# Steering_board.net
KiCad netlist of a schematic drawn in EAGLE
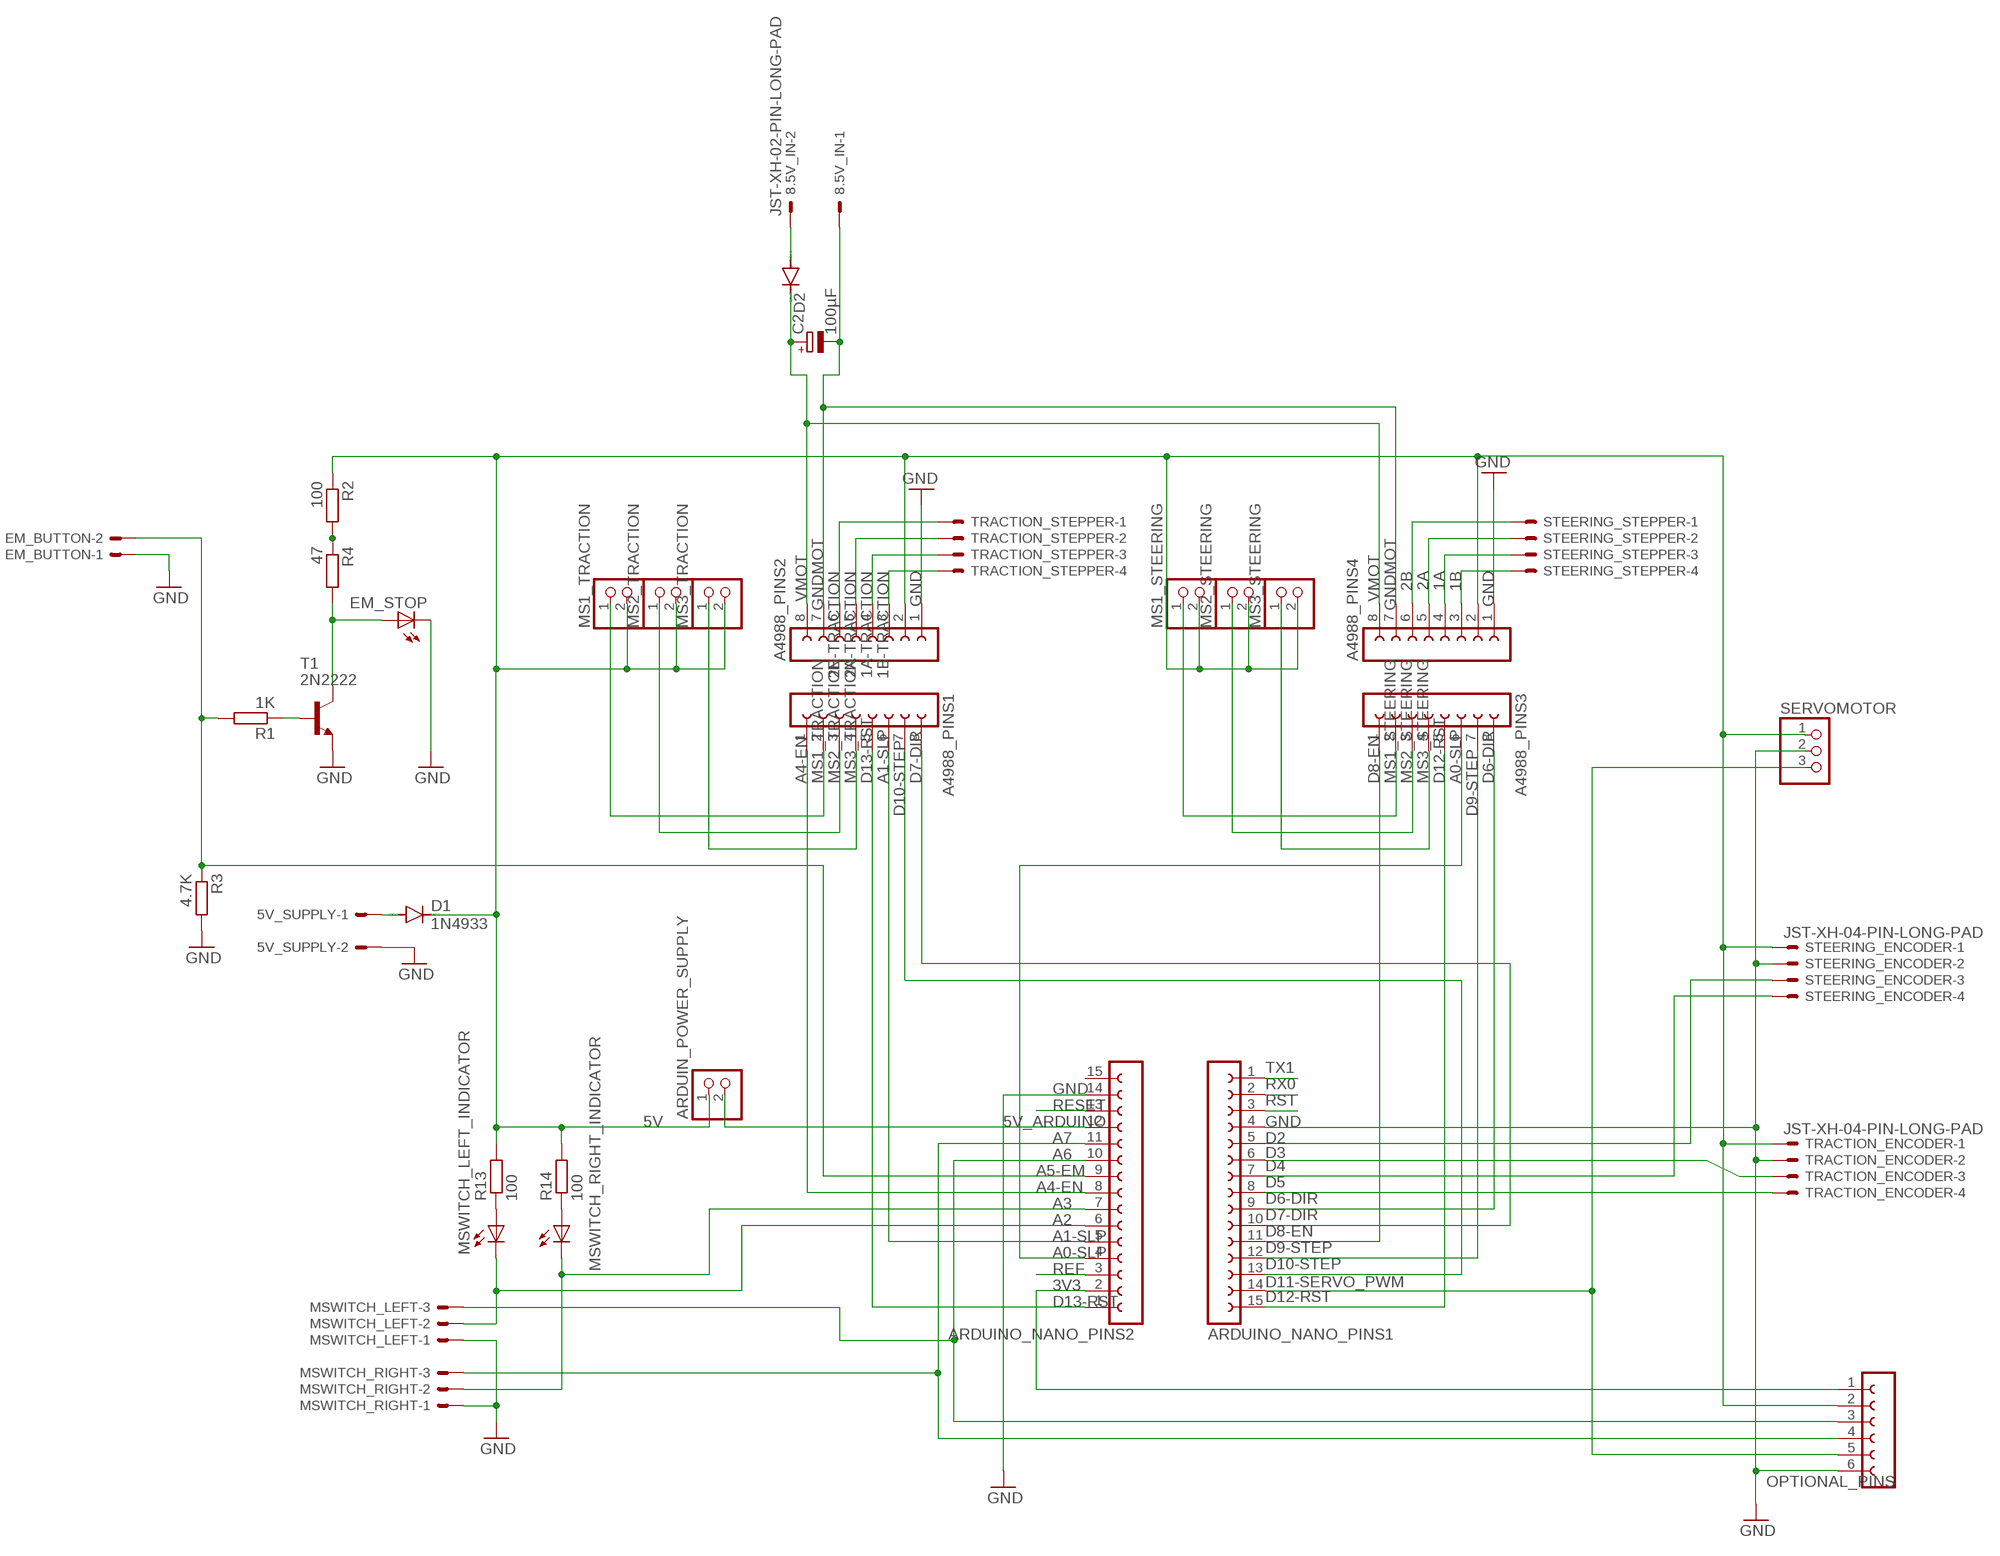
[diagram p0: schematic, sheet 1]

(export (version "E")
  (design (tool "Eeschema 10.0.6"))
  (components
    (comp (ref "5V_SUPPLY")
      (value "JST-XH-02-PIN-LONG-PAD")
      (footprint "eagle-import:JST-XH-02-PACKAGE-LONG-PAD")
      (libsource (lib "eagle-import") (part "JST-XH-02-PIN-LONG-PAD"))
    )
    (comp (ref "8.5V_IN")
      (value "JST-XH-02-PIN-LONG-PAD")
      (footprint "eagle-import:JST-XH-02-PACKAGE-LONG-PAD")
      (libsource (lib "eagle-import") (part "JST-XH-02-PIN-LONG-PAD"))
    )
    (comp (ref "A4988_PINS1")
      (value "FE08-1")
      (footprint "eagle-import:FE08")
      (libsource (lib "eagle-import") (part "FE08-1"))
    )
    (comp (ref "A4988_PINS2")
      (value "FE08-1")
      (footprint "eagle-import:FE08")
      (libsource (lib "eagle-import") (part "FE08-1"))
    )
    (comp (ref "A4988_PINS3")
      (value "FE08-1")
      (footprint "eagle-import:FE08")
      (libsource (lib "eagle-import") (part "FE08-1"))
    )
    (comp (ref "A4988_PINS4")
      (value "FE08-1")
      (footprint "eagle-import:FE08")
      (libsource (lib "eagle-import") (part "FE08-1"))
    )
    (comp (ref "ARDUINO_NANO_PINS1")
      (value "FE15-1")
      (footprint "eagle-import:FE15")
      (libsource (lib "eagle-import") (part "FE15-1"))
    )
    (comp (ref "ARDUINO_NANO_PINS2")
      (value "FE15-1")
      (footprint "eagle-import:FE15")
      (libsource (lib "eagle-import") (part "FE15-1"))
    )
    (comp (ref "ARDUIN_POWER_SUPPLY")
      (value "PINHD-1X2")
      (footprint "eagle-import:1X02")
      (libsource (lib "eagle-import") (part "PINHD-1X2"))
    )
    (comp (ref "C2")
      (value "100µF")
      (footprint "eagle-import:SANYO-OSCON_E")
      (libsource (lib "eagle-import") (part "CPOL-EUSANYO_E"))
    )
    (comp (ref "D1")
      (value "1N4933")
      (footprint "eagle-import:DO41-10")
      (libsource (lib "eagle-import") (part "1N4933"))
    )
    (comp (ref "D2")
      (value "DIODE-DO15-12")
      (footprint "eagle-import:DO15-12")
      (libsource (lib "eagle-import") (part "DIODE-DO15-12"))
    )
    (comp (ref "EM_BUTTON")
      (value "JST-XH-02-PIN-LONG-PAD")
      (footprint "eagle-import:JST-XH-02-PACKAGE-LONG-PAD")
      (libsource (lib "eagle-import") (part "JST-XH-02-PIN-LONG-PAD"))
    )
    (comp (ref "EM_STOP")
      (value "LED5MM")
      (footprint "eagle-import:LED5MM")
      (libsource (lib "eagle-import") (part "LED5MM"))
    )
    (comp (ref "MS1_STEERING")
      (value "PINHD-1X2")
      (footprint "eagle-import:1X02")
      (libsource (lib "eagle-import") (part "PINHD-1X2"))
    )
    (comp (ref "MS1_TRACTION")
      (value "PINHD-1X2")
      (footprint "eagle-import:1X02")
      (libsource (lib "eagle-import") (part "PINHD-1X2"))
    )
    (comp (ref "MS2_STEERING")
      (value "PINHD-1X2")
      (footprint "eagle-import:1X02")
      (libsource (lib "eagle-import") (part "PINHD-1X2"))
    )
    (comp (ref "MS2_TRACTION")
      (value "PINHD-1X2")
      (footprint "eagle-import:1X02")
      (libsource (lib "eagle-import") (part "PINHD-1X2"))
    )
    (comp (ref "MS3_STEERING")
      (value "PINHD-1X2")
      (footprint "eagle-import:1X02")
      (libsource (lib "eagle-import") (part "PINHD-1X2"))
    )
    (comp (ref "MS3_TRACTION")
      (value "PINHD-1X2")
      (footprint "eagle-import:1X02")
      (libsource (lib "eagle-import") (part "PINHD-1X2"))
    )
    (comp (ref "MSWITCH_LEFT")
      (value "JST-XH-03-PIN-LONG-PAD")
      (footprint "eagle-import:JST-XH-03-PACKAGE-LONG-PAD")
      (libsource (lib "eagle-import") (part "JST-XH-03-PIN-LONG-PAD"))
    )
    (comp (ref "MSWITCH_LEFT_INDICATOR")
      (value "LED5MM")
      (footprint "eagle-import:LED5MM")
      (libsource (lib "eagle-import") (part "LED5MM"))
    )
    (comp (ref "MSWITCH_RIGHT")
      (value "JST-XH-03-PIN-LONG-PAD")
      (footprint "eagle-import:JST-XH-03-PACKAGE-LONG-PAD")
      (libsource (lib "eagle-import") (part "JST-XH-03-PIN-LONG-PAD"))
    )
    (comp (ref "MSWITCH_RIGHT_INDICATOR")
      (value "LED5MM")
      (footprint "eagle-import:LED5MM")
      (libsource (lib "eagle-import") (part "LED5MM"))
    )
    (comp (ref "OPTIONAL_PINS")
      (value "FE06-1")
      (footprint "eagle-import:FE06")
      (libsource (lib "eagle-import") (part "FE06-1"))
    )
    (comp (ref "R1")
      (value "1K")
      (footprint "eagle-import:0207_7")
      (libsource (lib "eagle-import") (part "R-EU_0207/7"))
    )
    (comp (ref "R2")
      (value "100")
      (footprint "eagle-import:0207_7")
      (libsource (lib "eagle-import") (part "R-EU_0207/7"))
    )
    (comp (ref "R3")
      (value "4.7K")
      (footprint "eagle-import:0207_7")
      (libsource (lib "eagle-import") (part "R-EU_0207/7"))
    )
    (comp (ref "R4")
      (value "47")
      (footprint "eagle-import:0207_7")
      (libsource (lib "eagle-import") (part "R-EU_0207/7"))
    )
    (comp (ref "R13")
      (value "100")
      (footprint "eagle-import:0207_7")
      (libsource (lib "eagle-import") (part "R-EU_0207/7"))
    )
    (comp (ref "R14")
      (value "100")
      (footprint "eagle-import:0207_7")
      (libsource (lib "eagle-import") (part "R-EU_0207/7"))
    )
    (comp (ref "SERVOMOTOR")
      (value "PINHD-1X3")
      (footprint "eagle-import:1X03")
      (libsource (lib "eagle-import") (part "PINHD-1X3"))
    )
    (comp (ref "STEERING_ENCODER")
      (value "JST-XH-04-PIN-LONG-PAD")
      (footprint "eagle-import:JST-XH-04-PACKAGE-LONG-PAD")
      (libsource (lib "eagle-import") (part "JST-XH-04-PIN-LONG-PAD"))
    )
    (comp (ref "STEERING_STEPPER")
      (value "JST-XH-04-PIN-LONG-PAD")
      (footprint "eagle-import:JST-XH-04-PACKAGE-LONG-PAD")
      (libsource (lib "eagle-import") (part "JST-XH-04-PIN-LONG-PAD"))
    )
    (comp (ref "T1")
      (value "2N2222")
      (footprint "eagle-import:TO92-EBC-OVAL")
      (libsource (lib "eagle-import") (part "2N2222"))
    )
    (comp (ref "TRACTION_ENCODER")
      (value "JST-XH-04-PIN-LONG-PAD")
      (footprint "eagle-import:JST-XH-04-PACKAGE-LONG-PAD")
      (libsource (lib "eagle-import") (part "JST-XH-04-PIN-LONG-PAD"))
    )
    (comp (ref "TRACTION_STEPPER")
      (value "JST-XH-04-PIN-LONG-PAD")
      (footprint "eagle-import:JST-XH-04-PACKAGE-LONG-PAD")
      (libsource (lib "eagle-import") (part "JST-XH-04-PIN-LONG-PAD"))
    )
  )
  (nets
    (net (code "1") (name "/1A") (class "Default")
      (node (ref "A4988_PINS4") (pin "4") (pinfunction "4_4") (pintype "passive"))
      (node (ref "STEERING_STEPPER") (pin "3") (pinfunction "S_3") (pintype "passive"))
    )
    (net (code "2") (name "/1A-TRACTION") (class "Default")
      (node (ref "A4988_PINS2") (pin "4") (pinfunction "4_4") (pintype "passive"))
      (node (ref "TRACTION_STEPPER") (pin "3") (pinfunction "S_3") (pintype "passive"))
    )
    (net (code "3") (name "/1B") (class "Default")
      (node (ref "A4988_PINS4") (pin "3") (pinfunction "3_3") (pintype "passive"))
      (node (ref "STEERING_STEPPER") (pin "4") (pinfunction "S_4") (pintype "passive"))
    )
    (net (code "4") (name "/1B-TRACTION") (class "Default")
      (node (ref "A4988_PINS2") (pin "3") (pinfunction "3_3") (pintype "passive"))
      (node (ref "TRACTION_STEPPER") (pin "4") (pinfunction "S_4") (pintype "passive"))
    )
    (net (code "5") (name "/2A") (class "Default")
      (node (ref "A4988_PINS4") (pin "5") (pinfunction "5_5") (pintype "passive"))
      (node (ref "STEERING_STEPPER") (pin "2") (pinfunction "S_2") (pintype "passive"))
    )
    (net (code "6") (name "/2A-TRACTION") (class "Default")
      (node (ref "A4988_PINS2") (pin "5") (pinfunction "5_5") (pintype "passive"))
      (node (ref "TRACTION_STEPPER") (pin "2") (pinfunction "S_2") (pintype "passive"))
    )
    (net (code "7") (name "/2B") (class "Default")
      (node (ref "A4988_PINS4") (pin "6") (pinfunction "6_6") (pintype "passive"))
      (node (ref "STEERING_STEPPER") (pin "1") (pinfunction "S_1") (pintype "passive"))
    )
    (net (code "8") (name "/2B-TRACTION") (class "Default")
      (node (ref "A4988_PINS2") (pin "6") (pinfunction "6_6") (pintype "passive"))
      (node (ref "TRACTION_STEPPER") (pin "1") (pinfunction "S_1") (pintype "passive"))
    )
    (net (code "9") (name "/3V3") (class "Default")
      (node (ref "ARDUINO_NANO_PINS2") (pin "2") (pinfunction "2_2") (pintype "passive"))
      (node (ref "OPTIONAL_PINS") (pin "1") (pinfunction "1_1") (pintype "passive"))
    )
    (net (code "10") (name "/5V") (class "Default")
      (node (ref "A4988_PINS2") (pin "2") (pinfunction "2_2") (pintype "passive"))
      (node (ref "A4988_PINS4") (pin "2") (pinfunction "2_2") (pintype "passive"))
      (node (ref "ARDUIN_POWER_SUPPLY") (pin "1") (pinfunction "1_1") (pintype "passive"))
      (node (ref "D1") (pin "C") (pinfunction "C_C") (pintype "passive"))
      (node (ref "MS1_STEERING") (pin "2") (pinfunction "2_2") (pintype "passive"))
      (node (ref "MS1_TRACTION") (pin "2") (pinfunction "2_2") (pintype "passive"))
      (node (ref "MS2_STEERING") (pin "2") (pinfunction "2_2") (pintype "passive"))
      (node (ref "MS2_TRACTION") (pin "2") (pinfunction "2_2") (pintype "passive"))
      (node (ref "MS3_STEERING") (pin "2") (pinfunction "2_2") (pintype "passive"))
      (node (ref "MS3_TRACTION") (pin "2") (pinfunction "2_2") (pintype "passive"))
      (node (ref "OPTIONAL_PINS") (pin "2") (pinfunction "2_2") (pintype "passive"))
      (node (ref "R13") (pin "2") (pinfunction "2_2") (pintype "passive"))
      (node (ref "R14") (pin "2") (pinfunction "2_2") (pintype "passive"))
      (node (ref "R2") (pin "1") (pinfunction "1_1") (pintype "passive"))
      (node (ref "SERVOMOTOR") (pin "1") (pinfunction "1_1") (pintype "passive"))
      (node (ref "STEERING_ENCODER") (pin "1") (pinfunction "S_1") (pintype "passive"))
      (node (ref "TRACTION_ENCODER") (pin "1") (pinfunction "S_1") (pintype "passive"))
    )
    (net (code "11") (name "/5V_ARDUINO") (class "Default")
      (node (ref "ARDUINO_NANO_PINS2") (pin "12") (pinfunction "12_12") (pintype "passive"))
      (node (ref "ARDUIN_POWER_SUPPLY") (pin "2") (pinfunction "2_2") (pintype "passive"))
    )
    (net (code "12") (name "/A0-SLP") (class "Default")
      (node (ref "A4988_PINS3") (pin "6") (pinfunction "6_6") (pintype "passive"))
      (node (ref "ARDUINO_NANO_PINS2") (pin "4") (pinfunction "4_4") (pintype "passive"))
    )
    (net (code "13") (name "/A1-SLP") (class "Default")
      (node (ref "A4988_PINS1") (pin "6") (pinfunction "6_6") (pintype "passive"))
      (node (ref "ARDUINO_NANO_PINS2") (pin "5") (pinfunction "5_5") (pintype "passive"))
    )
    (net (code "14") (name "/A2") (class "Default")
      (node (ref "ARDUINO_NANO_PINS2") (pin "6") (pinfunction "6_6") (pintype "passive"))
      (node (ref "MSWITCH_LEFT") (pin "2") (pinfunction "S_2") (pintype "passive"))
      (node (ref "MSWITCH_LEFT_INDICATOR") (pin "K") (pinfunction "C_K") (pintype "passive"))
    )
    (net (code "15") (name "/A3") (class "Default")
      (node (ref "ARDUINO_NANO_PINS2") (pin "7") (pinfunction "7_7") (pintype "passive"))
      (node (ref "MSWITCH_RIGHT") (pin "2") (pinfunction "S_2") (pintype "passive"))
      (node (ref "MSWITCH_RIGHT_INDICATOR") (pin "K") (pinfunction "C_K") (pintype "passive"))
    )
    (net (code "16") (name "/A4-EN") (class "Default")
      (node (ref "A4988_PINS1") (pin "1") (pinfunction "1_1") (pintype "passive"))
      (node (ref "ARDUINO_NANO_PINS2") (pin "8") (pinfunction "8_8") (pintype "passive"))
    )
    (net (code "17") (name "/A5-EM") (class "Default")
      (node (ref "ARDUINO_NANO_PINS2") (pin "9") (pinfunction "9_9") (pintype "passive"))
      (node (ref "EM_BUTTON") (pin "2") (pinfunction "S_2") (pintype "passive"))
      (node (ref "R1") (pin "2") (pinfunction "2_2") (pintype "passive"))
      (node (ref "R3") (pin "1") (pinfunction "1_1") (pintype "passive"))
    )
    (net (code "18") (name "/A6") (class "Default")
      (node (ref "ARDUINO_NANO_PINS2") (pin "10") (pinfunction "10_10") (pintype "passive"))
      (node (ref "MSWITCH_LEFT") (pin "3") (pinfunction "S_3") (pintype "passive"))
      (node (ref "OPTIONAL_PINS") (pin "3") (pinfunction "3_3") (pintype "passive"))
    )
    (net (code "19") (name "/A7") (class "Default")
      (node (ref "ARDUINO_NANO_PINS2") (pin "11") (pinfunction "11_11") (pintype "passive"))
      (node (ref "MSWITCH_RIGHT") (pin "3") (pinfunction "S_3") (pintype "passive"))
      (node (ref "OPTIONAL_PINS") (pin "4") (pinfunction "4_4") (pintype "passive"))
    )
    (net (code "20") (name "/D2") (class "Default")
      (node (ref "ARDUINO_NANO_PINS1") (pin "5") (pinfunction "5_5") (pintype "passive"))
      (node (ref "STEERING_ENCODER") (pin "3") (pinfunction "S_3") (pintype "passive"))
    )
    (net (code "21") (name "/D3") (class "Default")
      (node (ref "ARDUINO_NANO_PINS1") (pin "6") (pinfunction "6_6") (pintype "passive"))
      (node (ref "TRACTION_ENCODER") (pin "3") (pinfunction "S_3") (pintype "passive"))
    )
    (net (code "22") (name "/D4") (class "Default")
      (node (ref "ARDUINO_NANO_PINS1") (pin "7") (pinfunction "7_7") (pintype "passive"))
      (node (ref "STEERING_ENCODER") (pin "4") (pinfunction "S_4") (pintype "passive"))
    )
    (net (code "23") (name "/D5") (class "Default")
      (node (ref "ARDUINO_NANO_PINS1") (pin "8") (pinfunction "8_8") (pintype "passive"))
      (node (ref "TRACTION_ENCODER") (pin "4") (pinfunction "S_4") (pintype "passive"))
    )
    (net (code "24") (name "/D6-DIR") (class "Default")
      (node (ref "A4988_PINS3") (pin "8") (pinfunction "8_8") (pintype "passive"))
      (node (ref "ARDUINO_NANO_PINS1") (pin "9") (pinfunction "9_9") (pintype "passive"))
    )
    (net (code "25") (name "/D7-DIR") (class "Default")
      (node (ref "A4988_PINS1") (pin "8") (pinfunction "8_8") (pintype "passive"))
      (node (ref "ARDUINO_NANO_PINS1") (pin "10") (pinfunction "10_10") (pintype "passive"))
    )
    (net (code "26") (name "/D8-EN") (class "Default")
      (node (ref "A4988_PINS3") (pin "1") (pinfunction "1_1") (pintype "passive"))
      (node (ref "ARDUINO_NANO_PINS1") (pin "11") (pinfunction "11_11") (pintype "passive"))
    )
    (net (code "27") (name "/D9-STEP") (class "Default")
      (node (ref "A4988_PINS3") (pin "7") (pinfunction "7_7") (pintype "passive"))
      (node (ref "ARDUINO_NANO_PINS1") (pin "12") (pinfunction "12_12") (pintype "passive"))
    )
    (net (code "28") (name "/D10-STEP") (class "Default")
      (node (ref "A4988_PINS1") (pin "7") (pinfunction "7_7") (pintype "passive"))
      (node (ref "ARDUINO_NANO_PINS1") (pin "13") (pinfunction "13_13") (pintype "passive"))
    )
    (net (code "29") (name "/D11-SERVO_PWM") (class "Default")
      (node (ref "ARDUINO_NANO_PINS1") (pin "14") (pinfunction "14_14") (pintype "passive"))
      (node (ref "OPTIONAL_PINS") (pin "5") (pinfunction "5_5") (pintype "passive"))
      (node (ref "SERVOMOTOR") (pin "3") (pinfunction "3_3") (pintype "passive"))
    )
    (net (code "30") (name "/D12-RST") (class "Default")
      (node (ref "A4988_PINS3") (pin "5") (pinfunction "5_5") (pintype "passive"))
      (node (ref "ARDUINO_NANO_PINS1") (pin "15") (pinfunction "15_15") (pintype "passive"))
    )
    (net (code "31") (name "/D13-RST") (class "Default")
      (node (ref "A4988_PINS1") (pin "5") (pinfunction "5_5") (pintype "passive"))
      (node (ref "ARDUINO_NANO_PINS2") (pin "1") (pinfunction "1_1") (pintype "passive"))
    )
    (net (code "32") (name "/GNDMOT") (class "Default")
      (node (ref "8.5V_IN") (pin "1") (pinfunction "S_1") (pintype "passive"))
      (node (ref "A4988_PINS2") (pin "7") (pinfunction "7_7") (pintype "passive"))
      (node (ref "A4988_PINS4") (pin "7") (pinfunction "7_7") (pintype "passive"))
      (node (ref "C2") (pin "-") (pinfunction "-_-") (pintype "passive"))
    )
    (net (code "33") (name "/MS1_STEERING") (class "Default")
      (node (ref "A4988_PINS3") (pin "2") (pinfunction "2_2") (pintype "passive"))
      (node (ref "MS1_STEERING") (pin "1") (pinfunction "1_1") (pintype "passive"))
    )
    (net (code "34") (name "/MS1_TRACTION") (class "Default")
      (node (ref "A4988_PINS1") (pin "2") (pinfunction "2_2") (pintype "passive"))
      (node (ref "MS1_TRACTION") (pin "1") (pinfunction "1_1") (pintype "passive"))
    )
    (net (code "35") (name "/MS2_STEERING") (class "Default")
      (node (ref "A4988_PINS3") (pin "3") (pinfunction "3_3") (pintype "passive"))
      (node (ref "MS2_STEERING") (pin "1") (pinfunction "1_1") (pintype "passive"))
    )
    (net (code "36") (name "/MS2_TRACTION") (class "Default")
      (node (ref "A4988_PINS1") (pin "3") (pinfunction "3_3") (pintype "passive"))
      (node (ref "MS2_TRACTION") (pin "1") (pinfunction "1_1") (pintype "passive"))
    )
    (net (code "37") (name "/MS3_STEERING") (class "Default")
      (node (ref "A4988_PINS3") (pin "4") (pinfunction "4_4") (pintype "passive"))
      (node (ref "MS3_STEERING") (pin "1") (pinfunction "1_1") (pintype "passive"))
    )
    (net (code "38") (name "/MS3_TRACTION") (class "Default")
      (node (ref "A4988_PINS1") (pin "4") (pinfunction "4_4") (pintype "passive"))
      (node (ref "MS3_TRACTION") (pin "1") (pinfunction "1_1") (pintype "passive"))
    )
    (net (code "39") (name "/REF") (class "Default")
      (node (ref "ARDUINO_NANO_PINS2") (pin "3") (pinfunction "3_3") (pintype "passive"))
    )
    (net (code "40") (name "/RESET") (class "Default")
      (node (ref "ARDUINO_NANO_PINS2") (pin "13") (pinfunction "13_13") (pintype "passive"))
    )
    (net (code "41") (name "/RST") (class "Default")
      (node (ref "ARDUINO_NANO_PINS1") (pin "3") (pinfunction "3_3") (pintype "passive"))
    )
    (net (code "42") (name "/RX0") (class "Default")
      (node (ref "ARDUINO_NANO_PINS1") (pin "2") (pinfunction "2_2") (pintype "passive"))
    )
    (net (code "43") (name "/TX1") (class "Default")
      (node (ref "ARDUINO_NANO_PINS1") (pin "1") (pinfunction "1_1") (pintype "passive"))
    )
    (net (code "44") (name "/VMOT") (class "Default")
      (node (ref "A4988_PINS2") (pin "8") (pinfunction "8_8") (pintype "passive"))
      (node (ref "A4988_PINS4") (pin "8") (pinfunction "8_8") (pintype "passive"))
      (node (ref "C2") (pin "+") (pinfunction "+_+") (pintype "passive"))
      (node (ref "D2") (pin "C") (pinfunction "C_C") (pintype "passive"))
    )
    (net (code "45") (name "GND") (class "Default")
      (node (ref "5V_SUPPLY") (pin "2") (pinfunction "S_2") (pintype "passive"))
      (node (ref "A4988_PINS2") (pin "1") (pinfunction "1_1") (pintype "passive"))
      (node (ref "A4988_PINS4") (pin "1") (pinfunction "1_1") (pintype "passive"))
      (node (ref "ARDUINO_NANO_PINS1") (pin "4") (pinfunction "4_4") (pintype "passive"))
      (node (ref "ARDUINO_NANO_PINS2") (pin "14") (pinfunction "14_14") (pintype "passive"))
      (node (ref "EM_BUTTON") (pin "1") (pinfunction "S_1") (pintype "passive"))
      (node (ref "EM_STOP") (pin "K") (pinfunction "C_K") (pintype "passive"))
      (node (ref "MSWITCH_LEFT") (pin "1") (pinfunction "S_1") (pintype "passive"))
      (node (ref "MSWITCH_RIGHT") (pin "1") (pinfunction "S_1") (pintype "passive"))
      (node (ref "OPTIONAL_PINS") (pin "6") (pinfunction "6_6") (pintype "passive"))
      (node (ref "R3") (pin "2") (pinfunction "2_2") (pintype "passive"))
      (node (ref "SERVOMOTOR") (pin "2") (pinfunction "2_2") (pintype "passive"))
      (node (ref "STEERING_ENCODER") (pin "2") (pinfunction "S_2") (pintype "passive"))
      (node (ref "T1") (pin "E") (pinfunction "E_E") (pintype "passive"))
      (node (ref "TRACTION_ENCODER") (pin "2") (pinfunction "S_2") (pintype "passive"))
    )
    (net (code "46") (name "Net-(5V_SUPPLYA-S)") (class "Default")
      (node (ref "5V_SUPPLY") (pin "1") (pinfunction "S_1") (pintype "passive"))
      (node (ref "D1") (pin "A") (pinfunction "A_A") (pintype "passive"))
    )
    (net (code "47") (name "Net-(8.5V_INB-S)") (class "Default")
      (node (ref "8.5V_IN") (pin "2") (pinfunction "S_2") (pintype "passive"))
      (node (ref "D2") (pin "A") (pinfunction "A_A") (pintype "passive"))
    )
    (net (code "48") (name "Net-(EM_STOP-PadA)") (class "Default")
      (node (ref "EM_STOP") (pin "A") (pinfunction "A_A") (pintype "passive"))
      (node (ref "R4") (pin "2") (pinfunction "2_2") (pintype "passive"))
      (node (ref "T1") (pin "C") (pinfunction "C_C") (pintype "passive"))
    )
    (net (code "49") (name "Net-(MSWITCH_LEFT_INDICATOR-PadA)") (class "Default")
      (node (ref "MSWITCH_LEFT_INDICATOR") (pin "A") (pinfunction "A_A") (pintype "passive"))
      (node (ref "R13") (pin "1") (pinfunction "1_1") (pintype "passive"))
    )
    (net (code "50") (name "Net-(MSWITCH_RIGHT_INDICATOR-PadA)") (class "Default")
      (node (ref "MSWITCH_RIGHT_INDICATOR") (pin "A") (pinfunction "A_A") (pintype "passive"))
      (node (ref "R14") (pin "1") (pinfunction "1_1") (pintype "passive"))
    )
    (net (code "51") (name "Net-(R1-Pad1)") (class "Default")
      (node (ref "R1") (pin "1") (pinfunction "1_1") (pintype "passive"))
      (node (ref "T1") (pin "B") (pinfunction "B_B") (pintype "passive"))
    )
    (net (code "52") (name "Net-(R2-Pad2)") (class "Default")
      (node (ref "R2") (pin "2") (pinfunction "2_2") (pintype "passive"))
      (node (ref "R4") (pin "1") (pinfunction "1_1") (pintype "passive"))
    )
    (net (code "53") (name "unconnected-(ARDUINO_NANO_PINS2-Pad15)") (class "Default")
      (node (ref "ARDUINO_NANO_PINS2") (pin "15") (pinfunction "15_15") (pintype "passive"))
    )
  )
)
